# pwrModule.net
KiCad netlist of a schematic drawn in EAGLE
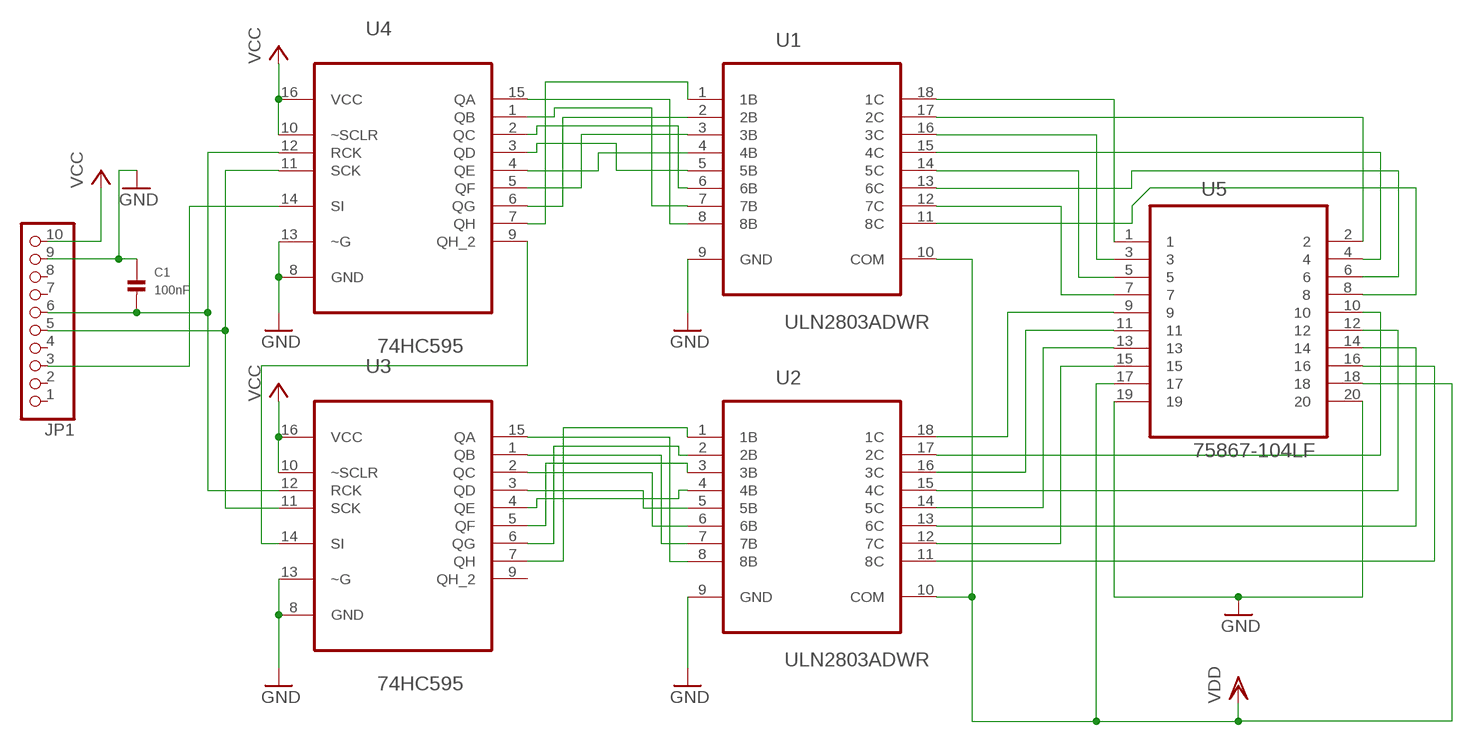
[diagram p0: schematic, sheet 1]

(export (version "E")
  (design (tool "Eeschema 10.0.6"))
  (components
    (comp (ref "C1")
      (value "100nF")
      (footprint "eagle-import:0805")
      (libsource (lib "eagle-import") (part "CAP_CERAMIC0805"))
    )
    (comp (ref "JP1")
      (value "PINHD-1X10/90")
      (footprint "eagle-import:1X10_90")
      (libsource (lib "eagle-import") (part "PINHD-1X10/90"))
    )
    (comp (ref "U1")
      (value "ULN2803ADWR")
      (footprint "eagle-import:SOIC127P1030X265-18N")
      (libsource (lib "eagle-import") (part "ULN2803ADWR"))
    )
    (comp (ref "U2")
      (value "ULN2803ADWR")
      (footprint "eagle-import:SOIC127P1030X265-18N")
      (libsource (lib "eagle-import") (part "ULN2803ADWR"))
    )
    (comp (ref "U3")
      (value "74HC595")
      (footprint "eagle-import:SOIC127P600X175-16N")
      (fields (field (name "MPN") "M74HC595RM13TR"))
      (libsource (lib "eagle-import") (part "M74HC595RM13TR"))
    )
    (comp (ref "U4")
      (value "74HC595")
      (footprint "eagle-import:SOIC127P600X175-16N")
      (fields (field (name "MPN") "M74HC595RM13TR"))
      (libsource (lib "eagle-import") (part "M74HC595RM13TR"))
    )
    (comp (ref "U5")
      (value "75867-104LF")
      (footprint "eagle-import:FCI_75867-104LF")
      (libsource (lib "eagle-import") (part "75867-104LF"))
    )
  )
  (nets
    (net (code "1") (name "GND") (class "Default")
      (node (ref "C1") (pin "1") (pinfunction "P$1_1") (pintype "passive"))
      (node (ref "JP1") (pin "9") (pinfunction "9_9") (pintype "passive"))
      (node (ref "U1") (pin "9") (pinfunction "GND_9") (pintype "passive"))
      (node (ref "U2") (pin "9") (pinfunction "GND_9") (pintype "passive"))
      (node (ref "U3") (pin "13") (pinfunction "~{G}_13") (pintype "input"))
      (node (ref "U3") (pin "8") (pinfunction "GND_8") (pintype "passive"))
      (node (ref "U4") (pin "13") (pinfunction "~{G}_13") (pintype "input"))
      (node (ref "U4") (pin "8") (pinfunction "GND_8") (pintype "passive"))
      (node (ref "U5") (pin "19") (pinfunction "19_19") (pintype "passive"))
      (node (ref "U5") (pin "20") (pinfunction "20_20") (pintype "passive"))
    )
    (net (code "2") (name "Net-(C1-P$2)") (class "Default")
      (node (ref "C1") (pin "2") (pinfunction "P$2_2") (pintype "passive"))
      (node (ref "JP1") (pin "6") (pinfunction "6_6") (pintype "passive"))
      (node (ref "U3") (pin "12") (pinfunction "RCK_12") (pintype "input"))
      (node (ref "U4") (pin "12") (pinfunction "RCK_12") (pintype "input"))
    )
    (net (code "3") (name "Net-(U1-1B)") (class "Default")
      (node (ref "U1") (pin "1") (pinfunction "1B_1") (pintype "input"))
      (node (ref "U4") (pin "7") (pinfunction "QH_7") (pintype "output"))
    )
    (net (code "4") (name "Net-(U1-1C)") (class "Default")
      (node (ref "U1") (pin "18") (pinfunction "1C_18") (pintype "output"))
      (node (ref "U5") (pin "1") (pinfunction "1_1") (pintype "passive"))
    )
    (net (code "5") (name "Net-(U1-2B)") (class "Default")
      (node (ref "U1") (pin "2") (pinfunction "2B_2") (pintype "input"))
      (node (ref "U4") (pin "6") (pinfunction "QG_6") (pintype "output"))
    )
    (net (code "6") (name "Net-(U1-2C)") (class "Default")
      (node (ref "U1") (pin "17") (pinfunction "2C_17") (pintype "output"))
      (node (ref "U5") (pin "2") (pinfunction "2_2") (pintype "passive"))
    )
    (net (code "7") (name "Net-(U1-3B)") (class "Default")
      (node (ref "U1") (pin "3") (pinfunction "3B_3") (pintype "input"))
      (node (ref "U4") (pin "5") (pinfunction "QF_5") (pintype "output"))
    )
    (net (code "8") (name "Net-(U1-3C)") (class "Default")
      (node (ref "U1") (pin "16") (pinfunction "3C_16") (pintype "output"))
      (node (ref "U5") (pin "3") (pinfunction "3_3") (pintype "passive"))
    )
    (net (code "9") (name "Net-(U1-4B)") (class "Default")
      (node (ref "U1") (pin "4") (pinfunction "4B_4") (pintype "input"))
      (node (ref "U4") (pin "4") (pinfunction "QE_4") (pintype "output"))
    )
    (net (code "10") (name "Net-(U1-4C)") (class "Default")
      (node (ref "U1") (pin "15") (pinfunction "4C_15") (pintype "output"))
      (node (ref "U5") (pin "4") (pinfunction "4_4") (pintype "passive"))
    )
    (net (code "11") (name "Net-(U1-5B)") (class "Default")
      (node (ref "U1") (pin "5") (pinfunction "5B_5") (pintype "input"))
      (node (ref "U4") (pin "3") (pinfunction "QD_3") (pintype "output"))
    )
    (net (code "12") (name "Net-(U1-5C)") (class "Default")
      (node (ref "U1") (pin "14") (pinfunction "5C_14") (pintype "output"))
      (node (ref "U5") (pin "5") (pinfunction "5_5") (pintype "passive"))
    )
    (net (code "13") (name "Net-(U1-6B)") (class "Default")
      (node (ref "U1") (pin "6") (pinfunction "6B_6") (pintype "input"))
      (node (ref "U4") (pin "2") (pinfunction "QC_2") (pintype "output"))
    )
    (net (code "14") (name "Net-(U1-6C)") (class "Default")
      (node (ref "U1") (pin "13") (pinfunction "6C_13") (pintype "output"))
      (node (ref "U5") (pin "6") (pinfunction "6_6") (pintype "passive"))
    )
    (net (code "15") (name "Net-(U1-7B)") (class "Default")
      (node (ref "U1") (pin "7") (pinfunction "7B_7") (pintype "input"))
      (node (ref "U4") (pin "1") (pinfunction "QB_1") (pintype "output"))
    )
    (net (code "16") (name "Net-(U1-7C)") (class "Default")
      (node (ref "U1") (pin "12") (pinfunction "7C_12") (pintype "output"))
      (node (ref "U5") (pin "7") (pinfunction "7_7") (pintype "passive"))
    )
    (net (code "17") (name "Net-(U1-8B)") (class "Default")
      (node (ref "U1") (pin "8") (pinfunction "8B_8") (pintype "input"))
      (node (ref "U4") (pin "15") (pinfunction "QA_15") (pintype "output"))
    )
    (net (code "18") (name "Net-(U1-8C)") (class "Default")
      (node (ref "U1") (pin "11") (pinfunction "8C_11") (pintype "output"))
      (node (ref "U5") (pin "8") (pinfunction "8_8") (pintype "passive"))
    )
    (net (code "19") (name "Net-(U2-1B)") (class "Default")
      (node (ref "U2") (pin "1") (pinfunction "1B_1") (pintype "input"))
      (node (ref "U3") (pin "7") (pinfunction "QH_7") (pintype "output"))
    )
    (net (code "20") (name "Net-(U2-1C)") (class "Default")
      (node (ref "U2") (pin "18") (pinfunction "1C_18") (pintype "output"))
      (node (ref "U5") (pin "9") (pinfunction "9_9") (pintype "passive"))
    )
    (net (code "21") (name "Net-(U2-2B)") (class "Default")
      (node (ref "U2") (pin "2") (pinfunction "2B_2") (pintype "input"))
      (node (ref "U3") (pin "6") (pinfunction "QG_6") (pintype "output"))
    )
    (net (code "22") (name "Net-(U2-2C)") (class "Default")
      (node (ref "U2") (pin "17") (pinfunction "2C_17") (pintype "output"))
      (node (ref "U5") (pin "10") (pinfunction "10_10") (pintype "passive"))
    )
    (net (code "23") (name "Net-(U2-3B)") (class "Default")
      (node (ref "U2") (pin "3") (pinfunction "3B_3") (pintype "input"))
      (node (ref "U3") (pin "5") (pinfunction "QF_5") (pintype "output"))
    )
    (net (code "24") (name "Net-(U2-3C)") (class "Default")
      (node (ref "U2") (pin "16") (pinfunction "3C_16") (pintype "output"))
      (node (ref "U5") (pin "11") (pinfunction "11_11") (pintype "passive"))
    )
    (net (code "25") (name "Net-(U2-4B)") (class "Default")
      (node (ref "U2") (pin "4") (pinfunction "4B_4") (pintype "input"))
      (node (ref "U3") (pin "4") (pinfunction "QE_4") (pintype "output"))
    )
    (net (code "26") (name "Net-(U2-4C)") (class "Default")
      (node (ref "U2") (pin "15") (pinfunction "4C_15") (pintype "output"))
      (node (ref "U5") (pin "12") (pinfunction "12_12") (pintype "passive"))
    )
    (net (code "27") (name "Net-(U2-5B)") (class "Default")
      (node (ref "U2") (pin "5") (pinfunction "5B_5") (pintype "input"))
      (node (ref "U3") (pin "3") (pinfunction "QD_3") (pintype "output"))
    )
    (net (code "28") (name "Net-(U2-5C)") (class "Default")
      (node (ref "U2") (pin "14") (pinfunction "5C_14") (pintype "output"))
      (node (ref "U5") (pin "13") (pinfunction "13_13") (pintype "passive"))
    )
    (net (code "29") (name "Net-(U2-6B)") (class "Default")
      (node (ref "U2") (pin "6") (pinfunction "6B_6") (pintype "input"))
      (node (ref "U3") (pin "2") (pinfunction "QC_2") (pintype "output"))
    )
    (net (code "30") (name "Net-(U2-6C)") (class "Default")
      (node (ref "U2") (pin "13") (pinfunction "6C_13") (pintype "output"))
      (node (ref "U5") (pin "14") (pinfunction "14_14") (pintype "passive"))
    )
    (net (code "31") (name "Net-(U2-7B)") (class "Default")
      (node (ref "U2") (pin "7") (pinfunction "7B_7") (pintype "input"))
      (node (ref "U3") (pin "1") (pinfunction "QB_1") (pintype "output"))
    )
    (net (code "32") (name "Net-(U2-7C)") (class "Default")
      (node (ref "U2") (pin "12") (pinfunction "7C_12") (pintype "output"))
      (node (ref "U5") (pin "15") (pinfunction "15_15") (pintype "passive"))
    )
    (net (code "33") (name "Net-(U2-8B)") (class "Default")
      (node (ref "U2") (pin "8") (pinfunction "8B_8") (pintype "input"))
      (node (ref "U3") (pin "15") (pinfunction "QA_15") (pintype "output"))
    )
    (net (code "34") (name "Net-(U2-8C)") (class "Default")
      (node (ref "U2") (pin "11") (pinfunction "8C_11") (pintype "output"))
      (node (ref "U5") (pin "16") (pinfunction "16_16") (pintype "passive"))
    )
    (net (code "35") (name "Net-(U3-SCK)") (class "Default")
      (node (ref "JP1") (pin "5") (pinfunction "5_5") (pintype "passive"))
      (node (ref "U3") (pin "11") (pinfunction "SCK_11") (pintype "input"))
      (node (ref "U4") (pin "11") (pinfunction "SCK_11") (pintype "input"))
    )
    (net (code "36") (name "Net-(U3-SI)") (class "Default")
      (node (ref "U3") (pin "14") (pinfunction "SI_14") (pintype "input"))
      (node (ref "U4") (pin "9") (pinfunction "QH_2_9") (pintype "output"))
    )
    (net (code "37") (name "Net-(U4-SI)") (class "Default")
      (node (ref "JP1") (pin "3") (pinfunction "3_3") (pintype "passive"))
      (node (ref "U4") (pin "14") (pinfunction "SI_14") (pintype "input"))
    )
    (net (code "38") (name "VCC") (class "Default")
      (node (ref "JP1") (pin "10") (pinfunction "10_10") (pintype "passive"))
      (node (ref "U3") (pin "10") (pinfunction "~{SCLR}_10") (pintype "input"))
      (node (ref "U3") (pin "16") (pinfunction "VCC_16") (pintype "power_in"))
      (node (ref "U4") (pin "10") (pinfunction "~{SCLR}_10") (pintype "input"))
      (node (ref "U4") (pin "16") (pinfunction "VCC_16") (pintype "power_in"))
    )
    (net (code "39") (name "VDD") (class "Default")
      (node (ref "U1") (pin "10") (pinfunction "COM_10") (pintype "output"))
      (node (ref "U2") (pin "10") (pinfunction "COM_10") (pintype "output"))
      (node (ref "U5") (pin "17") (pinfunction "17_17") (pintype "passive"))
      (node (ref "U5") (pin "18") (pinfunction "18_18") (pintype "passive"))
    )
    (net (code "40") (name "unconnected-(JP1-Pad1)") (class "Default")
      (node (ref "JP1") (pin "1") (pinfunction "1_1") (pintype "passive"))
    )
    (net (code "41") (name "unconnected-(JP1-Pad2)") (class "Default")
      (node (ref "JP1") (pin "2") (pinfunction "2_2") (pintype "passive"))
    )
    (net (code "42") (name "unconnected-(JP1-Pad4)") (class "Default")
      (node (ref "JP1") (pin "4") (pinfunction "4_4") (pintype "passive"))
    )
    (net (code "43") (name "unconnected-(JP1-Pad7)") (class "Default")
      (node (ref "JP1") (pin "7") (pinfunction "7_7") (pintype "passive"))
    )
    (net (code "44") (name "unconnected-(JP1-Pad8)") (class "Default")
      (node (ref "JP1") (pin "8") (pinfunction "8_8") (pintype "passive"))
    )
    (net (code "45") (name "unconnected-(U3-QH_2-Pad9)") (class "Default")
      (node (ref "U3") (pin "9") (pinfunction "QH_2_9") (pintype "output"))
    )
  )
)
